# flip_mask.net
KiCad netlist of a schematic drawn in EAGLE
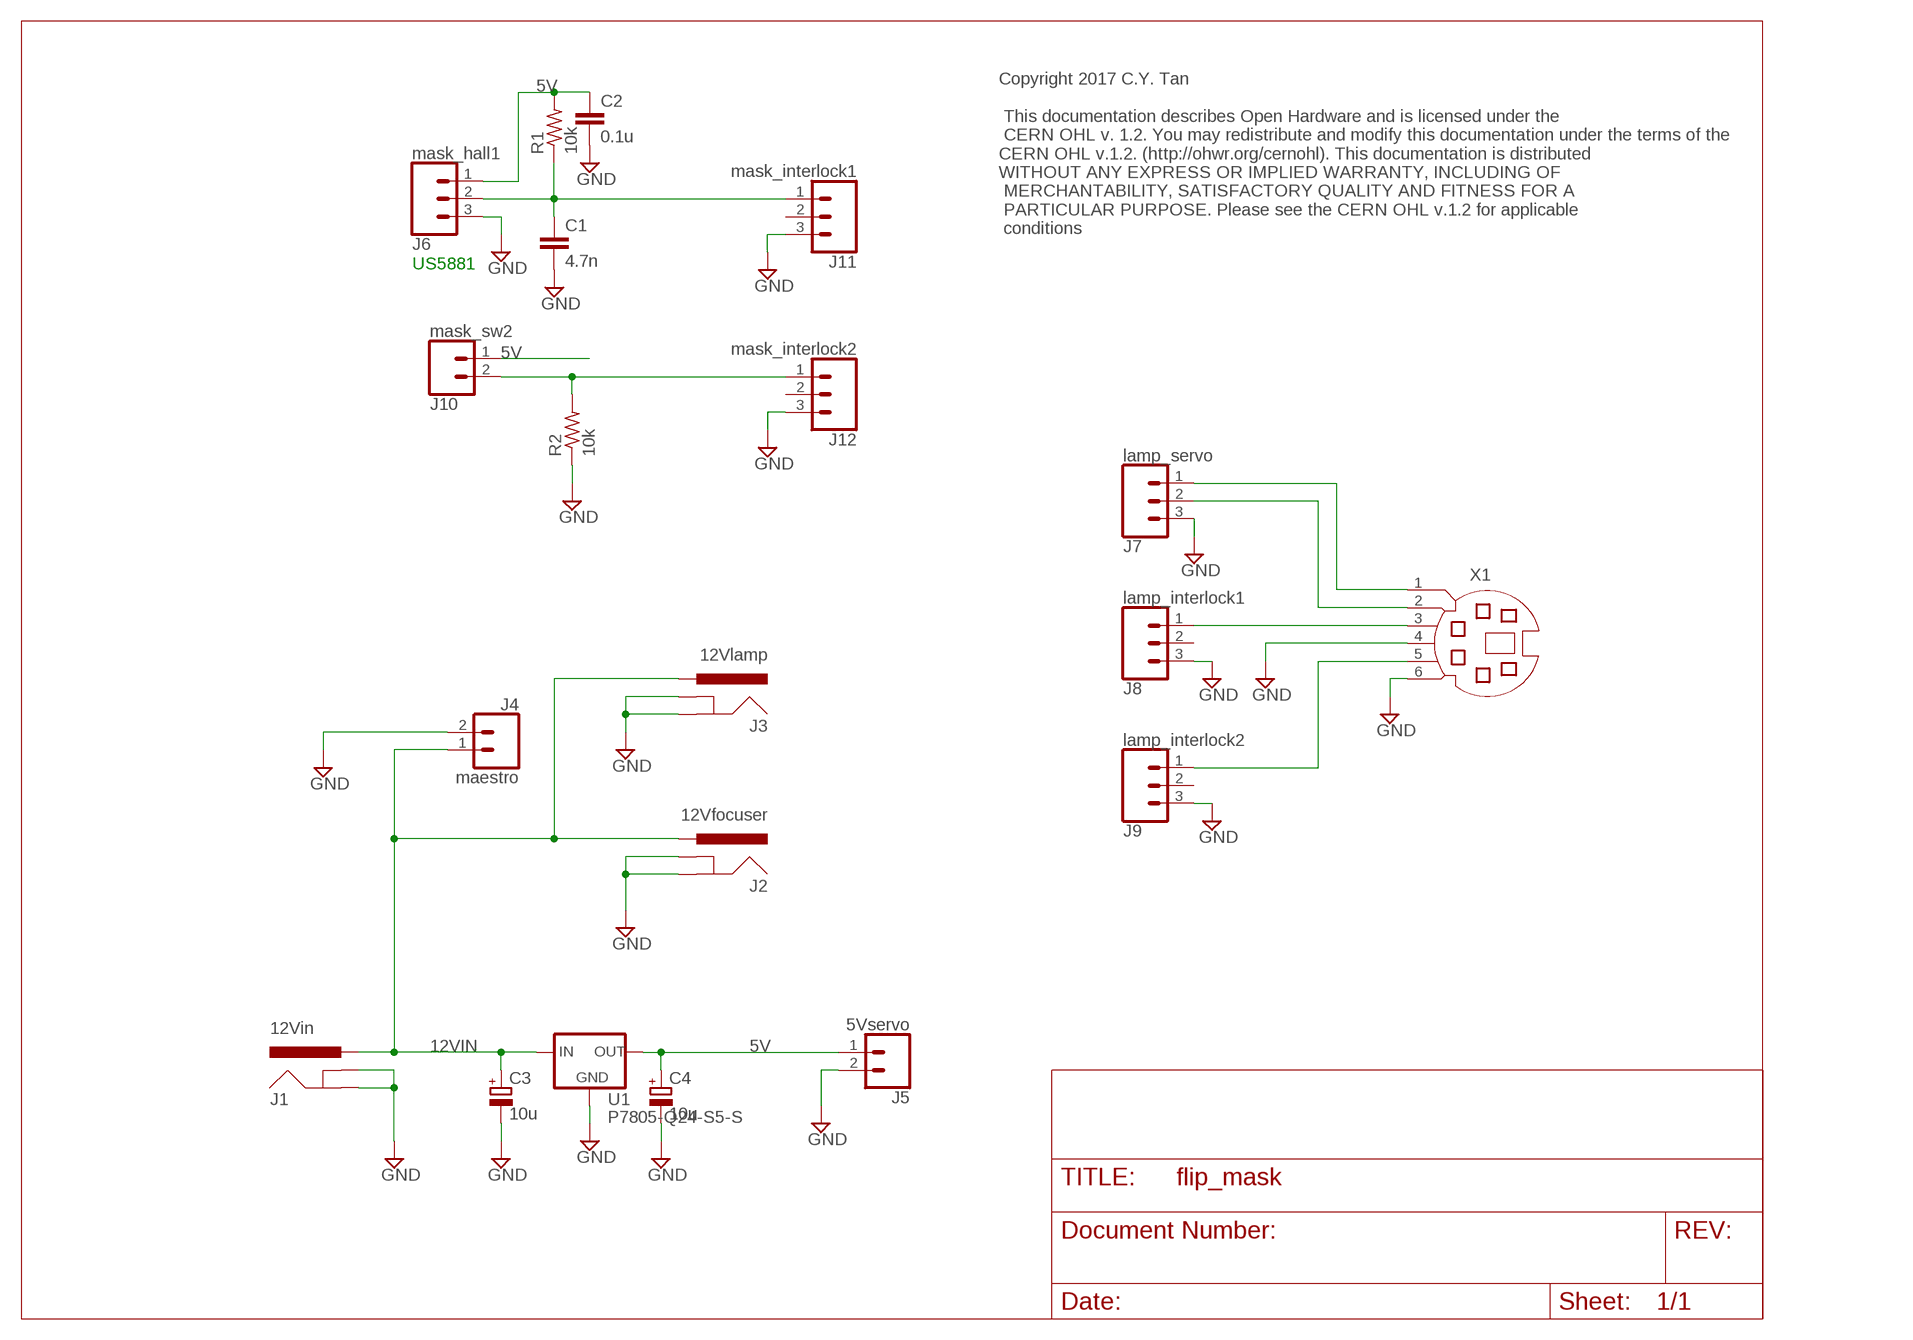
[diagram p0: schematic, sheet 1]

(export (version "E")
  (design (tool "Eeschema 10.0.6"))
  (components
    (comp (ref "C1")
      (value "4.7n")
      (footprint "eagle-import:CAP-PTH-5MM")
      (libsource (lib "eagle-import") (part "CAPPTH1"))
    )
    (comp (ref "C2")
      (value "0.1u")
      (footprint "eagle-import:CAP-PTH-5MM")
      (libsource (lib "eagle-import") (part "CAPPTH1"))
    )
    (comp (ref "C3")
      (value "10u")
      (footprint "eagle-import:E2,5-6")
      (libsource (lib "eagle-import") (part "CPOL-EUE2.5-6"))
    )
    (comp (ref "C4")
      (value "10u")
      (footprint "eagle-import:E2,5-6")
      (libsource (lib "eagle-import") (part "CPOL-EUE2.5-6"))
    )
    (comp (ref "J1")
      (value "12Vin")
      (footprint "eagle-import:POWER_JACK_PTH")
      (libsource (lib "eagle-import") (part "POWER_JACK"))
    )
    (comp (ref "J2")
      (value "12Vfocuser")
      (footprint "eagle-import:POWER_JACK_PTH")
      (libsource (lib "eagle-import") (part "POWER_JACK"))
    )
    (comp (ref "J3")
      (value "12Vlamp")
      (footprint "eagle-import:POWER_JACK_PTH")
      (libsource (lib "eagle-import") (part "POWER_JACK"))
    )
    (comp (ref "J4")
      (value "maestro")
      (footprint "eagle-import:1X02")
      (libsource (lib "eagle-import") (part "CONN_02"))
    )
    (comp (ref "J5")
      (value "5Vservo")
      (footprint "eagle-import:1X02")
      (libsource (lib "eagle-import") (part "CONN_02"))
    )
    (comp (ref "J6")
      (value "mask_hall1")
      (footprint "eagle-import:1X03")
      (libsource (lib "eagle-import") (part "CONN_03"))
    )
    (comp (ref "J7")
      (value "lamp_servo")
      (footprint "eagle-import:1X03")
      (libsource (lib "eagle-import") (part "CONN_03"))
    )
    (comp (ref "J8")
      (value "lamp_interlock1")
      (footprint "eagle-import:1X03")
      (libsource (lib "eagle-import") (part "CONN_03"))
    )
    (comp (ref "J9")
      (value "lamp_interlock2")
      (footprint "eagle-import:1X03")
      (libsource (lib "eagle-import") (part "CONN_03"))
    )
    (comp (ref "J10")
      (value "mask_sw2")
      (footprint "eagle-import:1X02")
      (libsource (lib "eagle-import") (part "CONN_02"))
    )
    (comp (ref "J11")
      (value "mask_interlock1")
      (footprint "eagle-import:1X03")
      (libsource (lib "eagle-import") (part "CONN_03"))
    )
    (comp (ref "J12")
      (value "mask_interlock2")
      (footprint "eagle-import:1X03")
      (libsource (lib "eagle-import") (part "CONN_03"))
    )
    (comp (ref "R1")
      (value "10k")
      (footprint "eagle-import:0207_10")
      (libsource (lib "eagle-import") (part "R-US_0207/10"))
    )
    (comp (ref "R2")
      (value "10k")
      (footprint "eagle-import:0207_10")
      (libsource (lib "eagle-import") (part "R-US_0207/10"))
    )
    (comp (ref "U1")
      (value "P7805-Q24-S5-S")
      (footprint "eagle-import:DC-DC_CONVERTER_78XX")
      (libsource (lib "eagle-import") (part "R-78E5.0-1.0"))
    )
    (comp (ref "X1")
      (value "MD06SS")
      (footprint "eagle-import:MDIN06SS")
      (libsource (lib "eagle-import") (part "MD06SS"))
    )
  )
  (nets
    (net (code "1") (name "/5V") (class "Default")
      (node (ref "C2") (pin "1") (pinfunction "1_1") (pintype "passive"))
      (node (ref "C4") (pin "+") (pinfunction "+_+") (pintype "passive"))
      (node (ref "J10") (pin "1") (pinfunction "1_1") (pintype "passive"))
      (node (ref "J5") (pin "1") (pinfunction "1_1") (pintype "passive"))
      (node (ref "J6") (pin "1") (pinfunction "1_1") (pintype "passive"))
      (node (ref "R1") (pin "2") (pinfunction "2_2") (pintype "passive"))
      (node (ref "U1") (pin "VOUT") (pinfunction "OUT_VOUT") (pintype "passive"))
    )
    (net (code "2") (name "/12VIN") (class "Default")
      (node (ref "C3") (pin "+") (pinfunction "+_+") (pintype "passive"))
      (node (ref "J1") (pin "PWR") (pinfunction "PWR_PWR") (pintype "bidirectional"))
      (node (ref "J2") (pin "PWR") (pinfunction "PWR_PWR") (pintype "bidirectional"))
      (node (ref "J3") (pin "PWR") (pinfunction "PWR_PWR") (pintype "bidirectional"))
      (node (ref "J4") (pin "1") (pinfunction "1_1") (pintype "passive"))
      (node (ref "U1") (pin "VIN") (pinfunction "IN_VIN") (pintype "input"))
    )
    (net (code "3") (name "GND") (class "Default")
      (node (ref "C1") (pin "2") (pinfunction "2_2") (pintype "passive"))
      (node (ref "C2") (pin "2") (pinfunction "2_2") (pintype "passive"))
      (node (ref "C3") (pin "-") (pinfunction "-_-") (pintype "passive"))
      (node (ref "C4") (pin "-") (pinfunction "-_-") (pintype "passive"))
      (node (ref "J1") (pin "GND") (pinfunction "GND_GND") (pintype "bidirectional"))
      (node (ref "J1") (pin "GNDBREAK") (pinfunction "GNDBREAK_GNDBREAK") (pintype "bidirectional"))
      (node (ref "J11") (pin "3") (pinfunction "3_3") (pintype "passive"))
      (node (ref "J12") (pin "3") (pinfunction "3_3") (pintype "passive"))
      (node (ref "J2") (pin "GND") (pinfunction "GND_GND") (pintype "bidirectional"))
      (node (ref "J2") (pin "GNDBREAK") (pinfunction "GNDBREAK_GNDBREAK") (pintype "bidirectional"))
      (node (ref "J3") (pin "GND") (pinfunction "GND_GND") (pintype "bidirectional"))
      (node (ref "J3") (pin "GNDBREAK") (pinfunction "GNDBREAK_GNDBREAK") (pintype "bidirectional"))
      (node (ref "J4") (pin "2") (pinfunction "2_2") (pintype "passive"))
      (node (ref "J5") (pin "2") (pinfunction "2_2") (pintype "passive"))
      (node (ref "J6") (pin "3") (pinfunction "3_3") (pintype "passive"))
      (node (ref "J7") (pin "3") (pinfunction "3_3") (pintype "passive"))
      (node (ref "J8") (pin "3") (pinfunction "3_3") (pintype "passive"))
      (node (ref "J9") (pin "3") (pinfunction "3_3") (pintype "passive"))
      (node (ref "R2") (pin "1") (pinfunction "1_1") (pintype "passive"))
      (node (ref "U1") (pin "GND") (pinfunction "GND_GND") (pintype "input"))
      (node (ref "X1") (pin "4") (pinfunction "4_4") (pintype "passive"))
      (node (ref "X1") (pin "6") (pinfunction "6_6") (pintype "passive"))
    )
    (net (code "4") (name "Net-(C1-Pad1)") (class "Default")
      (node (ref "C1") (pin "1") (pinfunction "1_1") (pintype "passive"))
      (node (ref "J11") (pin "1") (pinfunction "1_1") (pintype "passive"))
      (node (ref "J6") (pin "2") (pinfunction "2_2") (pintype "passive"))
      (node (ref "R1") (pin "1") (pinfunction "1_1") (pintype "passive"))
    )
    (net (code "5") (name "Net-(J7-Pad1)") (class "Default")
      (node (ref "J7") (pin "1") (pinfunction "1_1") (pintype "passive"))
      (node (ref "X1") (pin "1") (pinfunction "1_1") (pintype "passive"))
    )
    (net (code "6") (name "Net-(J7-Pad2)") (class "Default")
      (node (ref "J7") (pin "2") (pinfunction "2_2") (pintype "passive"))
      (node (ref "X1") (pin "2") (pinfunction "2_2") (pintype "passive"))
    )
    (net (code "7") (name "Net-(J8-Pad1)") (class "Default")
      (node (ref "J8") (pin "1") (pinfunction "1_1") (pintype "passive"))
      (node (ref "X1") (pin "3") (pinfunction "3_3") (pintype "passive"))
    )
    (net (code "8") (name "Net-(J9-Pad1)") (class "Default")
      (node (ref "J9") (pin "1") (pinfunction "1_1") (pintype "passive"))
      (node (ref "X1") (pin "5") (pinfunction "5_5") (pintype "passive"))
    )
    (net (code "9") (name "Net-(J10-Pad2)") (class "Default")
      (node (ref "J10") (pin "2") (pinfunction "2_2") (pintype "passive"))
      (node (ref "J12") (pin "1") (pinfunction "1_1") (pintype "passive"))
      (node (ref "R2") (pin "2") (pinfunction "2_2") (pintype "passive"))
    )
    (net (code "10") (name "unconnected-(J8-Pad2)") (class "Default")
      (node (ref "J8") (pin "2") (pinfunction "2_2") (pintype "passive"))
    )
    (net (code "11") (name "unconnected-(J9-Pad2)") (class "Default")
      (node (ref "J9") (pin "2") (pinfunction "2_2") (pintype "passive"))
    )
    (net (code "12") (name "unconnected-(J11-Pad2)") (class "Default")
      (node (ref "J11") (pin "2") (pinfunction "2_2") (pintype "passive"))
    )
    (net (code "13") (name "unconnected-(J12-Pad2)") (class "Default")
      (node (ref "J12") (pin "2") (pinfunction "2_2") (pintype "passive"))
    )
  )
)
